# Thermostat_8CH.net
KiCad netlist of a schematic drawn in Altium Designer
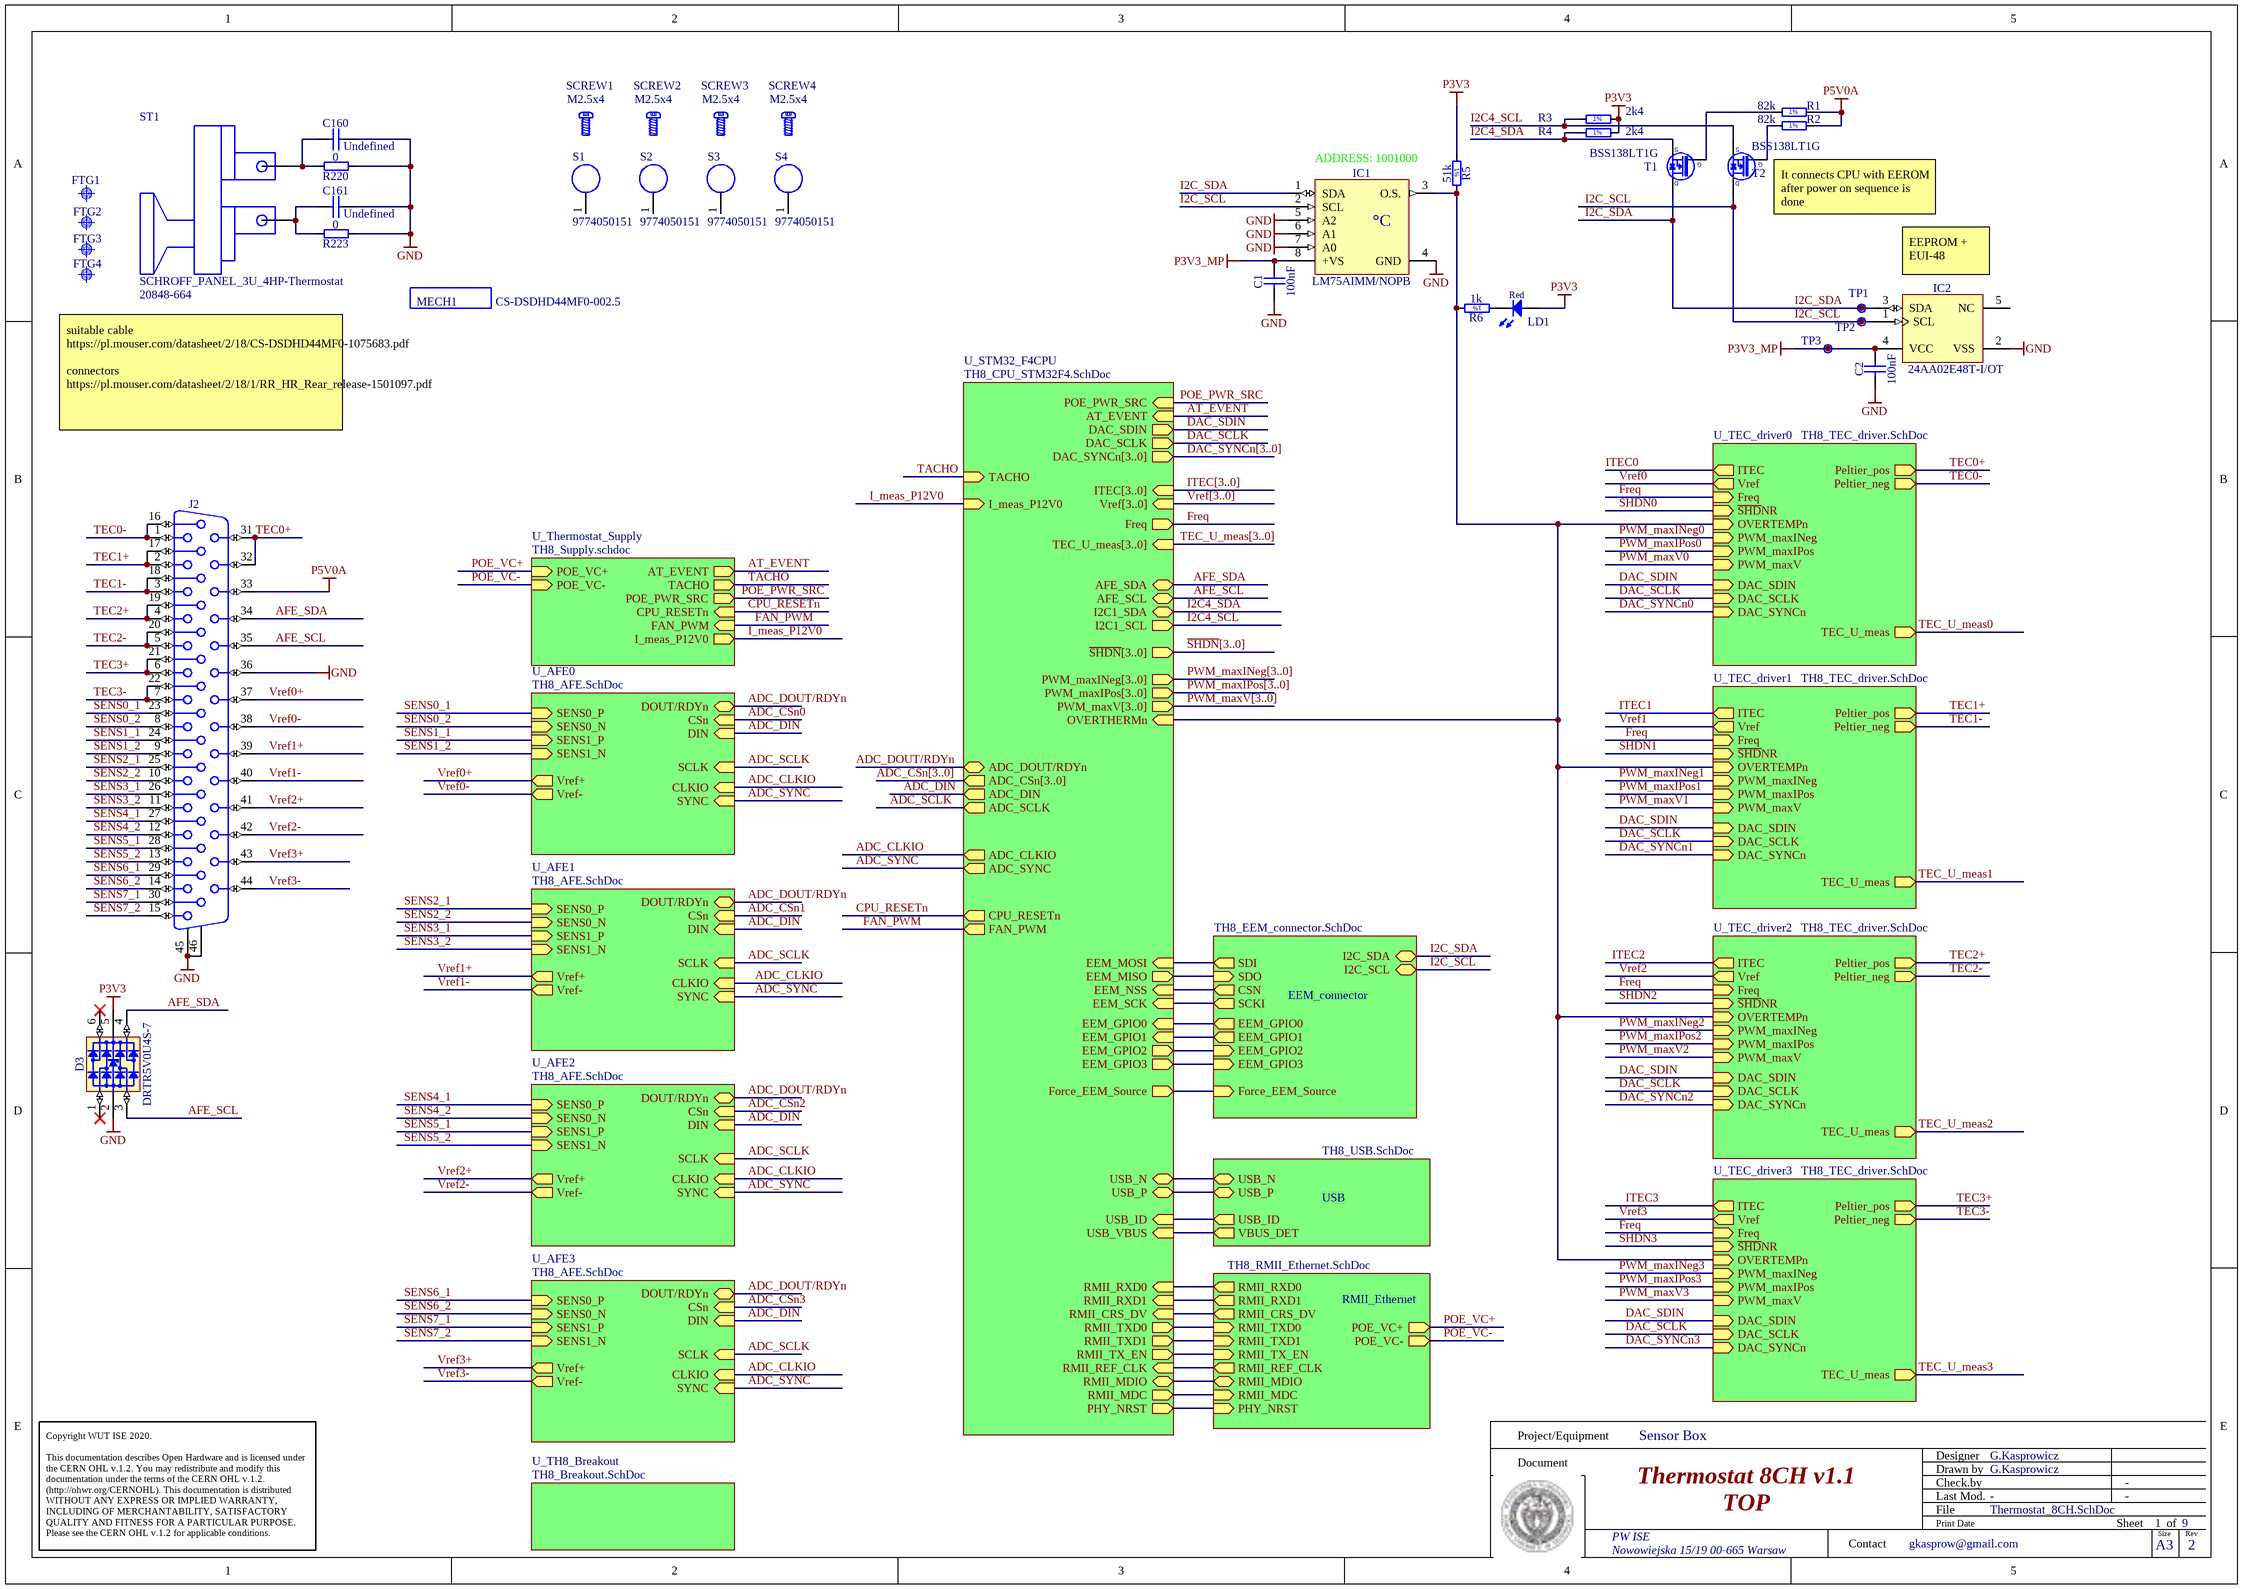
[diagram p0: Thermostat_8CH.SchDoc]

(export (version "E")
  (design (tool "Eeschema 10.0.6"))
  (components
    (comp (ref "C1")
      (value "100nF")
      (footprint "CAPC1005X55N")
      (description "Non-polarised capacitor")
      (fields
        (field (name "PART NUMBER") "CC0402_100NF_16V_10%_X5R")
        (field (name "VOLTAGE") "16V")
        (field (name "AUTHOR") "CERN DEM JLC")
      )
      (libsource (lib "Capacitors") (part "Capacitor - non polarized"))
    )
    (comp (ref "C2")
      (value "100nF")
      (footprint "CAPC1005X55N")
      (description "Non-polarised capacitor")
      (fields
        (field (name "PART NUMBER") "CC0402_100NF_16V_10%_X5R")
        (field (name "VOLTAGE") "16V")
        (field (name "AUTHOR") "CERN DEM JLC")
      )
      (libsource (lib "Capacitors") (part "Capacitor - non polarized"))
    )
    (comp (ref "C160")
      (value "Undefined")
      (footprint "CAPC2012X135N")
      (description "Non-polarised capacitor")
      (fields (field (name "PART NUMBER") "CC0805_NO-VALUE") (field (name "AUTHOR") "CERN DEM JLC"))
      (libsource (lib "Capacitors") (part "Capacitor - non polarized"))
    )
    (comp (ref "C161")
      (value "Undefined")
      (footprint "CAPC2012X135N")
      (description "Non-polarised capacitor")
      (fields (field (name "PART NUMBER") "CC0805_NO-VALUE") (field (name "AUTHOR") "CERN DEM JLC"))
      (libsource (lib "Capacitors") (part "Capacitor - non polarized"))
    )
    (comp (ref "D3")
      (value "DRTR5V0U4S-7")
      (footprint "SOT65P210X110-6N")
      (description "Integrated Quad Ultra-Low Capacitance ESD Protection")
      (fields (field (name "MANUFACTURER") "DIODES") (field (name "AUTHOR") "GK"))
      (libsource (lib "Diodes") (part "D_TVS_DRTR5V0U4S-7"))
    )
    (comp (ref "FTG1")
      (value "Use only in PCB")
      (footprint "FIDUCIAL_TOP_S100-200")
      (description "Fiducial Target")
      (fields (field (name "PART NUMBER") "FIDUCIAL_TARGET_S100-200") (field (name "AUTHOR") "CERN DEM JLC"))
      (libsource (lib "Eletro-mechanical") (part "Fiducial Target"))
    )
    (comp (ref "FTG2")
      (value "Use only in PCB")
      (footprint "FIDUCIAL_TOP_S100-200")
      (description "Fiducial Target")
      (fields (field (name "PART NUMBER") "FIDUCIAL_TARGET_S100-200") (field (name "AUTHOR") "CERN DEM JLC"))
      (libsource (lib "Eletro-mechanical") (part "Fiducial Target"))
    )
    (comp (ref "FTG3")
      (value "Use only in PCB")
      (footprint "FIDUCIAL_TOP_S100-200")
      (description "Fiducial Target")
      (fields (field (name "PART NUMBER") "FIDUCIAL_TARGET_S100-200") (field (name "AUTHOR") "CERN DEM JLC"))
      (libsource (lib "Eletro-mechanical") (part "Fiducial Target"))
    )
    (comp (ref "FTG4")
      (value "Use only in PCB")
      (footprint "FIDUCIAL_TOP_S100-200")
      (description "Fiducial Target")
      (fields (field (name "PART NUMBER") "FIDUCIAL_TARGET_S100-200") (field (name "AUTHOR") "CERN DEM JLC"))
      (libsource (lib "Eletro-mechanical") (part "Fiducial Target"))
    )
    (comp (ref "IC1")
      (value "LM75AIMM/NOPB")
      (footprint "SOP65P490X109-8N")
      (description "Digital Temperature Sensor and Thermal Watchdog with Two-Wire Interface")
      (fields (field (name "MANUFACTURER") "TEXAS INSTRUMENTS") (field (name "AUTHOR") "CERN DEM JLC"))
      (libsource (lib "ICs And Semiconductors") (part "LM75"))
    )
    (comp (ref "IC2")
      (value "24AA02E48T-I/OT")
      (footprint "SOT95P280X145-5N")
      (description "1.7V-5.5V, 2K I2C Serial EEPROM With EUI-48 Node Identity")
      (fields (field (name "MANUFACTURER") "MICROCHIP TECHNOLOGY") (field (name "AUTHOR") "CERN DEM MR"))
      (libsource (lib "ICs And Semiconductors") (part "24AA02E48T-I/OT"))
    )
    (comp (ref "J2")
      (value "D-Sub")
      (footprint "AMPHENOL_ICD44S13E6GX00LF")
      (description "Connector D-sub 44 Female")
      (fields
        (field (name "PART NUMBER") "AMPHENOL_ICD44S13E6GX00LF")
        (field (name "MANUFACTURER") "AMPHENOL")
        (field (name "AUTHOR") "CERN DEM BC")
      )
      (libsource (lib "Connectors") (part "Connector D-sub 44 Female"))
    )
    (comp (ref "LD1")
      (value "Red")
      (footprint "LED_KINGBRIGHT_KPH-1608SURCK")
      (description "LED Red 1C 2A")
      (fields
        (field (name "PART NUMBER") "LED_KINGBRIGHT_KPH-1608SURCK")
        (field (name "MANUFACTURER") "KINGBRIGHT")
        (field (name "AUTHOR") "CERN DEM JLC")
      )
      (libsource (lib "ICs And Semiconductors") (part "LED Red 1C 2A"))
    )
    (comp (ref "MECH1")
      (value "CS-DSDHD44MF0-002.5")
      (description "D-Sub Cables DELUXE HD44 M/F MOLDED 2.5'")
      (fields (field (name "MANUFACTURER") "Amphenol") (field (name "AUTHOR") "GK"))
      (libsource (lib "Mechanical") (part "Generic_mechanical"))
    )
    (comp (ref "R1")
      (value "82k")
      (footprint "RESC1608X55N")
      (description "Resistor - 1%")
      (fields
        (field (name "PART NUMBER") "R0603_82K_1%_0.1W_100PPM")
        (field (name "POWER") "0.1W")
        (field (name "AUTHOR") "CERN DEM JLC")
      )
      (libsource (lib "Resistors") (part "Resistor - 1%"))
    )
    (comp (ref "R2")
      (value "82k")
      (footprint "RESC1608X55N")
      (description "Resistor - 1%")
      (fields
        (field (name "PART NUMBER") "R0603_82K_1%_0.1W_100PPM")
        (field (name "POWER") "0.1W")
        (field (name "AUTHOR") "CERN DEM JLC")
      )
      (libsource (lib "Resistors") (part "Resistor - 1%"))
    )
    (comp (ref "R3")
      (value "2k4")
      (footprint "RESC1005X40N")
      (description "Resistor - 1%")
      (fields
        (field (name "PART NUMBER") "R0402_2K4_1%_0.0625W_100PPM")
        (field (name "POWER") "0.0625W")
        (field (name "AUTHOR") "CERN DEM JLC")
      )
      (libsource (lib "Resistors") (part "Resistor - 1%"))
    )
    (comp (ref "R4")
      (value "2k4")
      (footprint "RESC1005X40N")
      (description "Resistor - 1%")
      (fields
        (field (name "PART NUMBER") "R0402_2K4_1%_0.0625W_100PPM")
        (field (name "POWER") "0.0625W")
        (field (name "AUTHOR") "CERN DEM JLC")
      )
      (libsource (lib "Resistors") (part "Resistor - 1%"))
    )
    (comp (ref "R5")
      (value "51k")
      (footprint "RESC1005X40N")
      (description "Resistor - 1%")
      (fields
        (field (name "PART NUMBER") "R0402_51K_1%_0.0625W_100PPM")
        (field (name "POWER") "0.0625W")
        (field (name "AUTHOR") "CERN DEM JLC")
      )
      (libsource (lib "Resistors") (part "Resistor - 1%"))
    )
    (comp (ref "R6")
      (value "1k")
      (footprint "RESC1005X40N")
      (description "Resistor - 1%")
      (fields
        (field (name "PART NUMBER") "R0402_1K_1%_0.0625W_100PPM")
        (field (name "POWER") "0.0625W")
        (field (name "AUTHOR") "CERN DEM JLC")
      )
      (libsource (lib "Resistors") (part "Resistor - 1%"))
    )
    (comp (ref "R220")
      (value "0")
      (footprint "RESC1608X55N")
      (description "Resistor")
      (fields
        (field (name "PART NUMBER") "R0603_0R_JUMPER")
        (field (name "MANUFACTURER") "GENERIC")
        (field (name "AUTHOR") "CERN DEM JLC")
      )
      (libsource (lib "Resistors") (part "Resistor"))
    )
    (comp (ref "R223")
      (value "0")
      (footprint "RESC1608X55N")
      (description "Resistor")
      (fields
        (field (name "PART NUMBER") "R0603_0R_JUMPER")
        (field (name "MANUFACTURER") "GENERIC")
        (field (name "AUTHOR") "CERN DEM JLC")
      )
      (libsource (lib "Resistors") (part "Resistor"))
    )
    (comp (ref "S1")
      (value "9774050151")
      (footprint "9774050151")
      (description "WA-SMSI SMD Steel Spacer with internal Thread")
      (fields (field (name "MANUFACTURER") "Wurth Elektronik") (field (name "CREATED BY") "Baojun Chen"))
      (libsource (lib "Altium_SMSI_SMT_STEEL_SPACER_M2_5_THREAD_INTERNAL_rev15a") (part "WA-SMSI,  9774050151"))
    )
    (comp (ref "S2")
      (value "9774050151")
      (footprint "9774050151")
      (description "WA-SMSI SMD Steel Spacer with internal Thread")
      (fields (field (name "MANUFACTURER") "Wurth Elektronik") (field (name "CREATED BY") "Baojun Chen"))
      (libsource (lib "Altium_SMSI_SMT_STEEL_SPACER_M2_5_THREAD_INTERNAL_rev15a") (part "WA-SMSI,  9774050151"))
    )
    (comp (ref "S3")
      (value "9774050151")
      (footprint "9774050151")
      (description "WA-SMSI SMD Steel Spacer with internal Thread")
      (fields (field (name "MANUFACTURER") "Wurth Elektronik") (field (name "CREATED BY") "Baojun Chen"))
      (libsource (lib "Altium_SMSI_SMT_STEEL_SPACER_M2_5_THREAD_INTERNAL_rev15a") (part "WA-SMSI,  9774050151"))
    )
    (comp (ref "S4")
      (value "9774050151")
      (footprint "9774050151")
      (description "WA-SMSI SMD Steel Spacer with internal Thread")
      (fields (field (name "MANUFACTURER") "Wurth Elektronik") (field (name "CREATED BY") "Baojun Chen"))
      (libsource (lib "Altium_SMSI_SMT_STEEL_SPACER_M2_5_THREAD_INTERNAL_rev15a") (part "WA-SMSI,  9774050151"))
    )
    (comp (ref "SCREW1")
      (value "M2.5x4")
      (footprint "BOSSARD_BN5687-3061587_v")
      (description "Screw")
      (fields
        (field (name "PART NUMBER") "BOSSARD_BN5687-3061587_v")
        (field (name "MANUFACTURER") "BOSSARD")
        (field (name "AUTHOR") "CERN DEM JLC")
      )
      (libsource (lib "Eletro-mechanical") (part "Screw"))
    )
    (comp (ref "SCREW2")
      (value "M2.5x4")
      (footprint "BOSSARD_BN5687-3061587_v")
      (description "Screw")
      (fields
        (field (name "PART NUMBER") "BOSSARD_BN5687-3061587_v")
        (field (name "MANUFACTURER") "BOSSARD")
        (field (name "AUTHOR") "CERN DEM JLC")
      )
      (libsource (lib "Eletro-mechanical") (part "Screw"))
    )
    (comp (ref "SCREW3")
      (value "M2.5x4")
      (footprint "BOSSARD_BN5687-3061587_v")
      (description "Screw")
      (fields
        (field (name "PART NUMBER") "BOSSARD_BN5687-3061587_v")
        (field (name "MANUFACTURER") "BOSSARD")
        (field (name "AUTHOR") "CERN DEM JLC")
      )
      (libsource (lib "Eletro-mechanical") (part "Screw"))
    )
    (comp (ref "SCREW4")
      (value "M2.5x4")
      (footprint "BOSSARD_BN5687-3061587_v")
      (description "Screw")
      (fields
        (field (name "PART NUMBER") "BOSSARD_BN5687-3061587_v")
        (field (name "MANUFACTURER") "BOSSARD")
        (field (name "AUTHOR") "CERN DEM JLC")
      )
      (libsource (lib "Eletro-mechanical") (part "Screw"))
    )
    (comp (ref "ST1")
      (value "SCHROFF_PANEL_3U_4HP-Thermostat")
      (footprint "SCHROFF_PANEL_3HP_4U - Thermostat")
      (description "Schroff 3HP 4U EUROCARD Panel")
      (fields
        (field (name "MANUFACTURER") "Schroff")
        (field (name "MANUFACTURER PART NUMBER") "20818-017")
        (field (name "MANUFACTURER PART NUMBER 2") "20848-664")
      )
      (libsource (lib "Mechanical") (part "SCHROFF_PANEL_3U_4HP_Thermostat"))
    )
    (comp (ref "T1")
      (value "BSS138LT1G")
      (footprint "SOT95P240X110-3N")
      (description "N-CHANNEL MOSFET WITH DIODE")
      (fields (field (name "MANUFACTURER") "ON SEMICONDUCTOR") (field (name "AUTHOR") "CERN DEM JLC"))
      (libsource (lib "ICs And Semiconductors") (part "N-MOSFET-D 1G 2S 3D"))
    )
    (comp (ref "T2")
      (value "BSS138LT1G")
      (footprint "SOT95P240X110-3N")
      (description "N-CHANNEL MOSFET WITH DIODE")
      (fields (field (name "MANUFACTURER") "ON SEMICONDUCTOR") (field (name "AUTHOR") "CERN DEM JLC"))
      (libsource (lib "ICs And Semiconductors") (part "N-MOSFET-D 1G 2S 3D"))
    )
    (comp (ref "TP1")
      (value "Test Point")
      (footprint "TPS127")
      (fields (field (name "PART NUMBER") "SMD_PAD_1.27X1.27MM") (field (name "AUTHOR") "CERN DEM JLC"))
      (libsource (lib "Eletro-mechanical") (part "Test Point"))
    )
    (comp (ref "TP2")
      (value "Test Point")
      (footprint "TPS127")
      (fields (field (name "PART NUMBER") "SMD_PAD_1.27X1.27MM") (field (name "AUTHOR") "CERN DEM JLC"))
      (libsource (lib "Eletro-mechanical") (part "Test Point"))
    )
    (comp (ref "TP3")
      (value "Test Point")
      (footprint "TPS127")
      (fields (field (name "PART NUMBER") "SMD_PAD_1.27X1.27MM") (field (name "AUTHOR") "CERN DEM JLC"))
      (libsource (lib "Eletro-mechanical") (part "Test Point"))
    )
  )
  (nets
    (net (code "11") (name "/AFE_SCL") (class "Default")
      (node (ref "D3") (pin "3") (pinfunction "I/O2_3") (pintype "bidirectional"))
      (node (ref "J2") (pin "35") (pinfunction "35_35") (pintype "bidirectional"))
    )
    (net (code "12") (name "/AFE_SDA") (class "Default")
      (node (ref "D3") (pin "4") (pinfunction "I/O3_4") (pintype "bidirectional"))
      (node (ref "J2") (pin "34") (pinfunction "34_34") (pintype "bidirectional"))
    )
    (net (code "31") (name "/I2C4_SCL") (class "Default")
      (node (ref "R3") (pin "1") (pinfunction "1_1") (pintype "passive"))
      (node (ref "T2") (pin "2") (pinfunction "S_2") (pintype "passive"))
    )
    (net (code "32") (name "/I2C4_SDA") (class "Default")
      (node (ref "R4") (pin "1") (pinfunction "1_1") (pintype "passive"))
      (node (ref "T1") (pin "2") (pinfunction "S_2") (pintype "passive"))
    )
    (net (code "33") (name "/I2C_SCL") (class "Default")
      (node (ref "IC1") (pin "2") (pinfunction "SCL_2") (pintype "input"))
      (node (ref "IC2") (pin "1") (pinfunction "SCL_1") (pintype "input"))
      (node (ref "T2") (pin "3") (pinfunction "D_3") (pintype "passive"))
      (node (ref "TP2") (pin "1") (pinfunction "1_1") (pintype "bidirectional"))
    )
    (net (code "34") (name "/I2C_SDA") (class "Default")
      (node (ref "IC1") (pin "1") (pinfunction "SDA_1") (pintype "bidirectional"))
      (node (ref "IC2") (pin "3") (pinfunction "SDA_3") (pintype "bidirectional"))
      (node (ref "T1") (pin "3") (pinfunction "D_3") (pintype "passive"))
      (node (ref "TP1") (pin "1") (pinfunction "1_1") (pintype "bidirectional"))
    )
    (net (code "41") (name "/OVERTEMPn") (class "Default")
      (node (ref "IC1") (pin "3") (pinfunction "O.S._3") (pintype "output"))
      (node (ref "R5") (pin "2") (pinfunction "2_2") (pintype "passive"))
      (node (ref "R6") (pin "2") (pinfunction "2_2") (pintype "passive"))
    )
    (net (code "72") (name "/SENS0_1") (class "Default")
      (node (ref "J2") (pin "23") (pinfunction "23_23") (pintype "bidirectional"))
    )
    (net (code "73") (name "/SENS0_2") (class "Default")
      (node (ref "J2") (pin "8") (pinfunction "8_8") (pintype "bidirectional"))
    )
    (net (code "74") (name "/SENS1_1") (class "Default")
      (node (ref "J2") (pin "24") (pinfunction "24_24") (pintype "bidirectional"))
    )
    (net (code "75") (name "/SENS1_2") (class "Default")
      (node (ref "J2") (pin "9") (pinfunction "9_9") (pintype "bidirectional"))
    )
    (net (code "76") (name "/SENS2_1") (class "Default")
      (node (ref "J2") (pin "25") (pinfunction "25_25") (pintype "bidirectional"))
    )
    (net (code "77") (name "/SENS2_2") (class "Default")
      (node (ref "J2") (pin "10") (pinfunction "10_10") (pintype "bidirectional"))
    )
    (net (code "78") (name "/SENS3_1") (class "Default")
      (node (ref "J2") (pin "26") (pinfunction "26_26") (pintype "bidirectional"))
    )
    (net (code "79") (name "/SENS3_2") (class "Default")
      (node (ref "J2") (pin "11") (pinfunction "11_11") (pintype "bidirectional"))
    )
    (net (code "80") (name "/SENS4_1") (class "Default")
      (node (ref "J2") (pin "27") (pinfunction "27_27") (pintype "bidirectional"))
    )
    (net (code "81") (name "/SENS4_2") (class "Default")
      (node (ref "J2") (pin "12") (pinfunction "12_12") (pintype "bidirectional"))
    )
    (net (code "82") (name "/SENS5_1") (class "Default")
      (node (ref "J2") (pin "28") (pinfunction "28_28") (pintype "bidirectional"))
    )
    (net (code "83") (name "/SENS5_2") (class "Default")
      (node (ref "J2") (pin "13") (pinfunction "13_13") (pintype "bidirectional"))
    )
    (net (code "84") (name "/SENS6_1") (class "Default")
      (node (ref "J2") (pin "29") (pinfunction "29_29") (pintype "bidirectional"))
    )
    (net (code "85") (name "/SENS6_2") (class "Default")
      (node (ref "J2") (pin "14") (pinfunction "14_14") (pintype "bidirectional"))
    )
    (net (code "86") (name "/SENS7_1") (class "Default")
      (node (ref "J2") (pin "30") (pinfunction "30_30") (pintype "bidirectional"))
    )
    (net (code "87") (name "/SENS7_2") (class "Default")
      (node (ref "J2") (pin "15") (pinfunction "15_15") (pintype "bidirectional"))
    )
    (net (code "89") (name "/TEC0+") (class "Default")
      (node (ref "J2") (pin "31") (pinfunction "31_31") (pintype "bidirectional"))
      (node (ref "J2") (pin "32") (pinfunction "32_32") (pintype "bidirectional"))
    )
    (net (code "90") (name "/TEC0-") (class "Default")
      (node (ref "J2") (pin "1") (pinfunction "1_1") (pintype "bidirectional"))
      (node (ref "J2") (pin "16") (pinfunction "16_16") (pintype "bidirectional"))
    )
    (net (code "91") (name "/TEC1+") (class "Default")
      (node (ref "J2") (pin "17") (pinfunction "17_17") (pintype "bidirectional"))
      (node (ref "J2") (pin "2") (pinfunction "2_2") (pintype "bidirectional"))
    )
    (net (code "92") (name "/TEC1-") (class "Default")
      (node (ref "J2") (pin "18") (pinfunction "18_18") (pintype "bidirectional"))
      (node (ref "J2") (pin "3") (pinfunction "3_3") (pintype "bidirectional"))
    )
    (net (code "93") (name "/TEC2+") (class "Default")
      (node (ref "J2") (pin "19") (pinfunction "19_19") (pintype "bidirectional"))
      (node (ref "J2") (pin "4") (pinfunction "4_4") (pintype "bidirectional"))
    )
    (net (code "94") (name "/TEC2-") (class "Default")
      (node (ref "J2") (pin "20") (pinfunction "20_20") (pintype "bidirectional"))
      (node (ref "J2") (pin "5") (pinfunction "5_5") (pintype "bidirectional"))
    )
    (net (code "95") (name "/TEC3+") (class "Default")
      (node (ref "J2") (pin "21") (pinfunction "21_21") (pintype "bidirectional"))
      (node (ref "J2") (pin "6") (pinfunction "6_6") (pintype "bidirectional"))
    )
    (net (code "96") (name "/TEC3-") (class "Default")
      (node (ref "J2") (pin "22") (pinfunction "22_22") (pintype "bidirectional"))
      (node (ref "J2") (pin "7") (pinfunction "7_7") (pintype "bidirectional"))
    )
    (net (code "107") (name "/Vref0+") (class "Default")
      (node (ref "J2") (pin "37") (pinfunction "37_37") (pintype "bidirectional"))
    )
    (net (code "108") (name "/Vref0-") (class "Default")
      (node (ref "J2") (pin "38") (pinfunction "38_38") (pintype "bidirectional"))
    )
    (net (code "110") (name "/Vref1+") (class "Default")
      (node (ref "J2") (pin "39") (pinfunction "39_39") (pintype "bidirectional"))
    )
    (net (code "111") (name "/Vref1-") (class "Default")
      (node (ref "J2") (pin "40") (pinfunction "40_40") (pintype "bidirectional"))
    )
    (net (code "113") (name "/Vref2+") (class "Default")
      (node (ref "J2") (pin "41") (pinfunction "41_41") (pintype "bidirectional"))
    )
    (net (code "114") (name "/Vref2-") (class "Default")
      (node (ref "J2") (pin "42") (pinfunction "42_42") (pintype "bidirectional"))
    )
    (net (code "116") (name "/Vref3+") (class "Default")
      (node (ref "J2") (pin "43") (pinfunction "43_43") (pintype "bidirectional"))
    )
    (net (code "117") (name "/Vref3-") (class "Default")
      (node (ref "J2") (pin "44") (pinfunction "44_44") (pintype "bidirectional"))
    )
    (net (code "124") (name "GND") (class "Default")
      (node (ref "C1") (pin "1") (pinfunction "1_1") (pintype "passive"))
      (node (ref "C160") (pin "2") (pinfunction "2_2") (pintype "passive"))
      (node (ref "C161") (pin "2") (pinfunction "2_2") (pintype "passive"))
      (node (ref "C2") (pin "1") (pinfunction "1_1") (pintype "passive"))
      (node (ref "D3") (pin "2") (pinfunction "GND_2") (pintype "power_in"))
      (node (ref "IC1") (pin "4") (pinfunction "GND_4") (pintype "power_in"))
      (node (ref "IC1") (pin "5") (pinfunction "A2_5") (pintype "input"))
      (node (ref "IC1") (pin "6") (pinfunction "A1_6") (pintype "input"))
      (node (ref "IC1") (pin "7") (pinfunction "A0_7") (pintype "input"))
      (node (ref "IC2") (pin "2") (pinfunction "VSS_2") (pintype "power_in"))
      (node (ref "J2") (pin "36") (pinfunction "36_36") (pintype "bidirectional"))
      (node (ref "J2") (pin "45") (pinfunction "45_45") (pintype "passive"))
      (node (ref "J2") (pin "46") (pinfunction "46_46") (pintype "passive"))
      (node (ref "R220") (pin "1") (pinfunction "1_1") (pintype "passive"))
      (node (ref "R223") (pin "1") (pinfunction "1_1") (pintype "passive"))
    )
    (net (code "125") (name "Net-(C160-Pad1)") (class "Default")
      (node (ref "C160") (pin "1") (pinfunction "1_1") (pintype "passive"))
      (node (ref "R220") (pin "2") (pinfunction "2_2") (pintype "passive"))
      (node (ref "ST1") (pin "1") (pinfunction "1_1") (pintype "passive"))
    )
    (net (code "126") (name "Net-(C161-Pad1)") (class "Default")
      (node (ref "C161") (pin "1") (pinfunction "1_1") (pintype "passive"))
      (node (ref "R223") (pin "2") (pinfunction "2_2") (pintype "passive"))
      (node (ref "ST1") (pin "0") (pinfunction "0_0") (pintype "passive"))
    )
    (net (code "127") (name "Net-(LD1-C)") (class "Default")
      (node (ref "LD1") (pin "1") (pinfunction "C_1") (pintype "passive"))
      (node (ref "R6") (pin "1") (pinfunction "1_1") (pintype "passive"))
    )
    (net (code "128") (name "Net-(T1-G)") (class "Default")
      (node (ref "R1") (pin "1") (pinfunction "1_1") (pintype "passive"))
      (node (ref "T1") (pin "1") (pinfunction "G_1") (pintype "passive"))
    )
    (net (code "129") (name "Net-(T2-G)") (class "Default")
      (node (ref "R2") (pin "1") (pinfunction "1_1") (pintype "passive"))
      (node (ref "T2") (pin "1") (pinfunction "G_1") (pintype "passive"))
    )
    (net (code "130") (name "P3V3") (class "Default")
      (node (ref "D3") (pin "5") (pinfunction "VBUS_5") (pintype "power_in"))
      (node (ref "LD1") (pin "2") (pinfunction "A_2") (pintype "passive"))
      (node (ref "R3") (pin "2") (pinfunction "2_2") (pintype "passive"))
      (node (ref "R4") (pin "2") (pinfunction "2_2") (pintype "passive"))
      (node (ref "R5") (pin "1") (pinfunction "1_1") (pintype "passive"))
    )
    (net (code "131") (name "P3V3_MP") (class "Default")
      (node (ref "C1") (pin "2") (pinfunction "2_2") (pintype "passive"))
      (node (ref "C2") (pin "2") (pinfunction "2_2") (pintype "passive"))
      (node (ref "IC1") (pin "8") (pinfunction "+VS_8") (pintype "power_in"))
      (node (ref "IC2") (pin "4") (pinfunction "VCC_4") (pintype "power_in"))
      (node (ref "TP3") (pin "1") (pinfunction "1_1") (pintype "bidirectional"))
    )
    (net (code "132") (name "P5V0A") (class "Default")
      (node (ref "J2") (pin "33") (pinfunction "33_33") (pintype "bidirectional"))
      (node (ref "R1") (pin "2") (pinfunction "2_2") (pintype "passive"))
      (node (ref "R2") (pin "2") (pinfunction "2_2") (pintype "passive"))
    )
    (net (code "133") (name "unconnected-(D3-I{slash}O1-Pad1)") (class "Default")
      (node (ref "D3") (pin "1") (pinfunction "I/O1_1") (pintype "bidirectional+no_connect"))
    )
    (net (code "134") (name "unconnected-(D3-I{slash}O4-Pad6)") (class "Default")
      (node (ref "D3") (pin "6") (pinfunction "I/O4_6") (pintype "bidirectional+no_connect"))
    )
    (net (code "135") (name "unconnected-(IC2-NC-Pad5)") (class "Default")
      (node (ref "IC2") (pin "5") (pinfunction "NC_5") (pintype "passive"))
    )
    (net (code "136") (name "unconnected-(S1-Pad1)") (class "Default")
      (node (ref "S1") (pin "1") (pinfunction "1_1") (pintype "passive"))
    )
    (net (code "137") (name "unconnected-(S2-Pad1)") (class "Default")
      (node (ref "S2") (pin "1") (pinfunction "1_1") (pintype "passive"))
    )
    (net (code "138") (name "unconnected-(S3-Pad1)") (class "Default")
      (node (ref "S3") (pin "1") (pinfunction "1_1") (pintype "passive"))
    )
    (net (code "139") (name "unconnected-(S4-Pad1)") (class "Default")
      (node (ref "S4") (pin "1") (pinfunction "1_1") (pintype "passive"))
    )
  )
)
